# LCD.net
KiCad netlist of a schematic drawn in Altium Designer
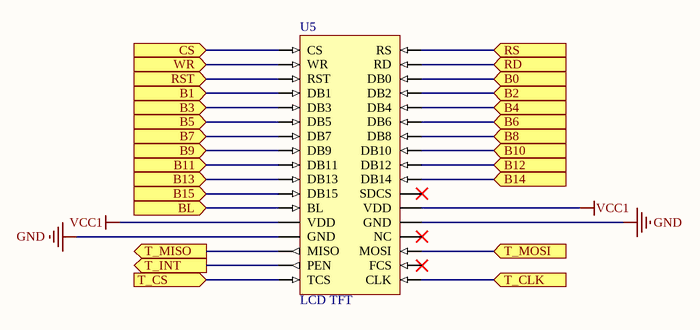
[diagram p0: LCD.SchDoc]

(export (version "E")
  (design (tool "Eeschema 10.0.6"))
  (components
    (comp (ref "U5")
      (value "LCD TFT")
      (footprint "LCD TFT 2.8\" Parallel 8/16-bit")
      (description "LCD TFT 16-bit")
      (libsource (lib "My Library") (part "LCD TFT 16-bit"))
    )
  )
  (nets
    (net (code "1") (name "/B0") (class "Default")
      (node (ref "U5") (pin "32") (pinfunction "DB0_32") (pintype "input"))
    )
    (net (code "2") (name "/B1") (class "Default")
      (node (ref "U5") (pin "4") (pinfunction "DB1_4") (pintype "input"))
    )
    (net (code "3") (name "/B2") (class "Default")
      (node (ref "U5") (pin "31") (pinfunction "DB2_31") (pintype "input"))
    )
    (net (code "4") (name "/B3") (class "Default")
      (node (ref "U5") (pin "5") (pinfunction "DB3_5") (pintype "input"))
    )
    (net (code "5") (name "/B4") (class "Default")
      (node (ref "U5") (pin "30") (pinfunction "DB4_30") (pintype "input"))
    )
    (net (code "6") (name "/B5") (class "Default")
      (node (ref "U5") (pin "6") (pinfunction "DB5_6") (pintype "input"))
    )
    (net (code "7") (name "/B6") (class "Default")
      (node (ref "U5") (pin "29") (pinfunction "DB6_29") (pintype "input"))
    )
    (net (code "8") (name "/B7") (class "Default")
      (node (ref "U5") (pin "7") (pinfunction "DB7_7") (pintype "input"))
    )
    (net (code "9") (name "/B8") (class "Default")
      (node (ref "U5") (pin "28") (pinfunction "DB8_28") (pintype "input"))
    )
    (net (code "10") (name "/B9") (class "Default")
      (node (ref "U5") (pin "8") (pinfunction "DB9_8") (pintype "input"))
    )
    (net (code "11") (name "/B10") (class "Default")
      (node (ref "U5") (pin "27") (pinfunction "DB10_27") (pintype "input"))
    )
    (net (code "12") (name "/B11") (class "Default")
      (node (ref "U5") (pin "9") (pinfunction "DB11_9") (pintype "input"))
    )
    (net (code "13") (name "/B12") (class "Default")
      (node (ref "U5") (pin "26") (pinfunction "DB12_26") (pintype "input"))
    )
    (net (code "14") (name "/B13") (class "Default")
      (node (ref "U5") (pin "10") (pinfunction "DB13_10") (pintype "input"))
    )
    (net (code "15") (name "/B14") (class "Default")
      (node (ref "U5") (pin "25") (pinfunction "DB14_25") (pintype "input"))
    )
    (net (code "16") (name "/B15") (class "Default")
      (node (ref "U5") (pin "11") (pinfunction "DB15_11") (pintype "input"))
    )
    (net (code "17") (name "/BL") (class "Default")
      (node (ref "U5") (pin "12") (pinfunction "BL_12") (pintype "input"))
    )
    (net (code "18") (name "/CS") (class "Default")
      (node (ref "U5") (pin "1") (pinfunction "CS_1") (pintype "input"))
    )
    (net (code "19") (name "/RD") (class "Default")
      (node (ref "U5") (pin "33") (pinfunction "RD_33") (pintype "input"))
    )
    (net (code "20") (name "/RS") (class "Default")
      (node (ref "U5") (pin "34") (pinfunction "RS_34") (pintype "input"))
    )
    (net (code "21") (name "/RST") (class "Default")
      (node (ref "U5") (pin "3") (pinfunction "RST_3") (pintype "input"))
    )
    (net (code "22") (name "/T_CLK") (class "Default")
      (node (ref "U5") (pin "18") (pinfunction "CLK_18") (pintype "input"))
    )
    (net (code "23") (name "/T_CS") (class "Default")
      (node (ref "U5") (pin "17") (pinfunction "TCS_17") (pintype "input"))
    )
    (net (code "24") (name "/T_INT") (class "Default")
      (node (ref "U5") (pin "16") (pinfunction "PEN_16") (pintype "output"))
    )
    (net (code "25") (name "/T_MISO") (class "Default")
      (node (ref "U5") (pin "15") (pinfunction "MISO_15") (pintype "output"))
    )
    (net (code "26") (name "/T_MOSI") (class "Default")
      (node (ref "U5") (pin "20") (pinfunction "MOSI_20") (pintype "input"))
    )
    (net (code "27") (name "/WR") (class "Default")
      (node (ref "U5") (pin "2") (pinfunction "WR_2") (pintype "input"))
    )
    (net (code "28") (name "GND") (class "Default")
      (node (ref "U5") (pin "14") (pinfunction "GND_14") (pintype "power_in"))
      (node (ref "U5") (pin "22") (pinfunction "GND_22") (pintype "power_in"))
    )
    (net (code "29") (name "VCC1") (class "Default")
      (node (ref "U5") (pin "13") (pinfunction "VDD_13") (pintype "power_in"))
      (node (ref "U5") (pin "23") (pinfunction "VDD_23") (pintype "power_in"))
    )
    (net (code "30") (name "unconnected-(U5-FCS-Pad19)") (class "Default")
      (node (ref "U5") (pin "19") (pinfunction "FCS_19") (pintype "input+no_connect"))
    )
    (net (code "31") (name "unconnected-(U5-NC-Pad21)") (class "Default")
      (node (ref "U5") (pin "21") (pinfunction "NC_21") (pintype "passive+no_connect"))
    )
    (net (code "32") (name "unconnected-(U5-SDCS-Pad24)") (class "Default")
      (node (ref "U5") (pin "24") (pinfunction "SDCS_24") (pintype "passive+no_connect"))
    )
  )
)
